# POWER_SUPPLY.net
KiCad netlist of a schematic drawn in Altium Designer
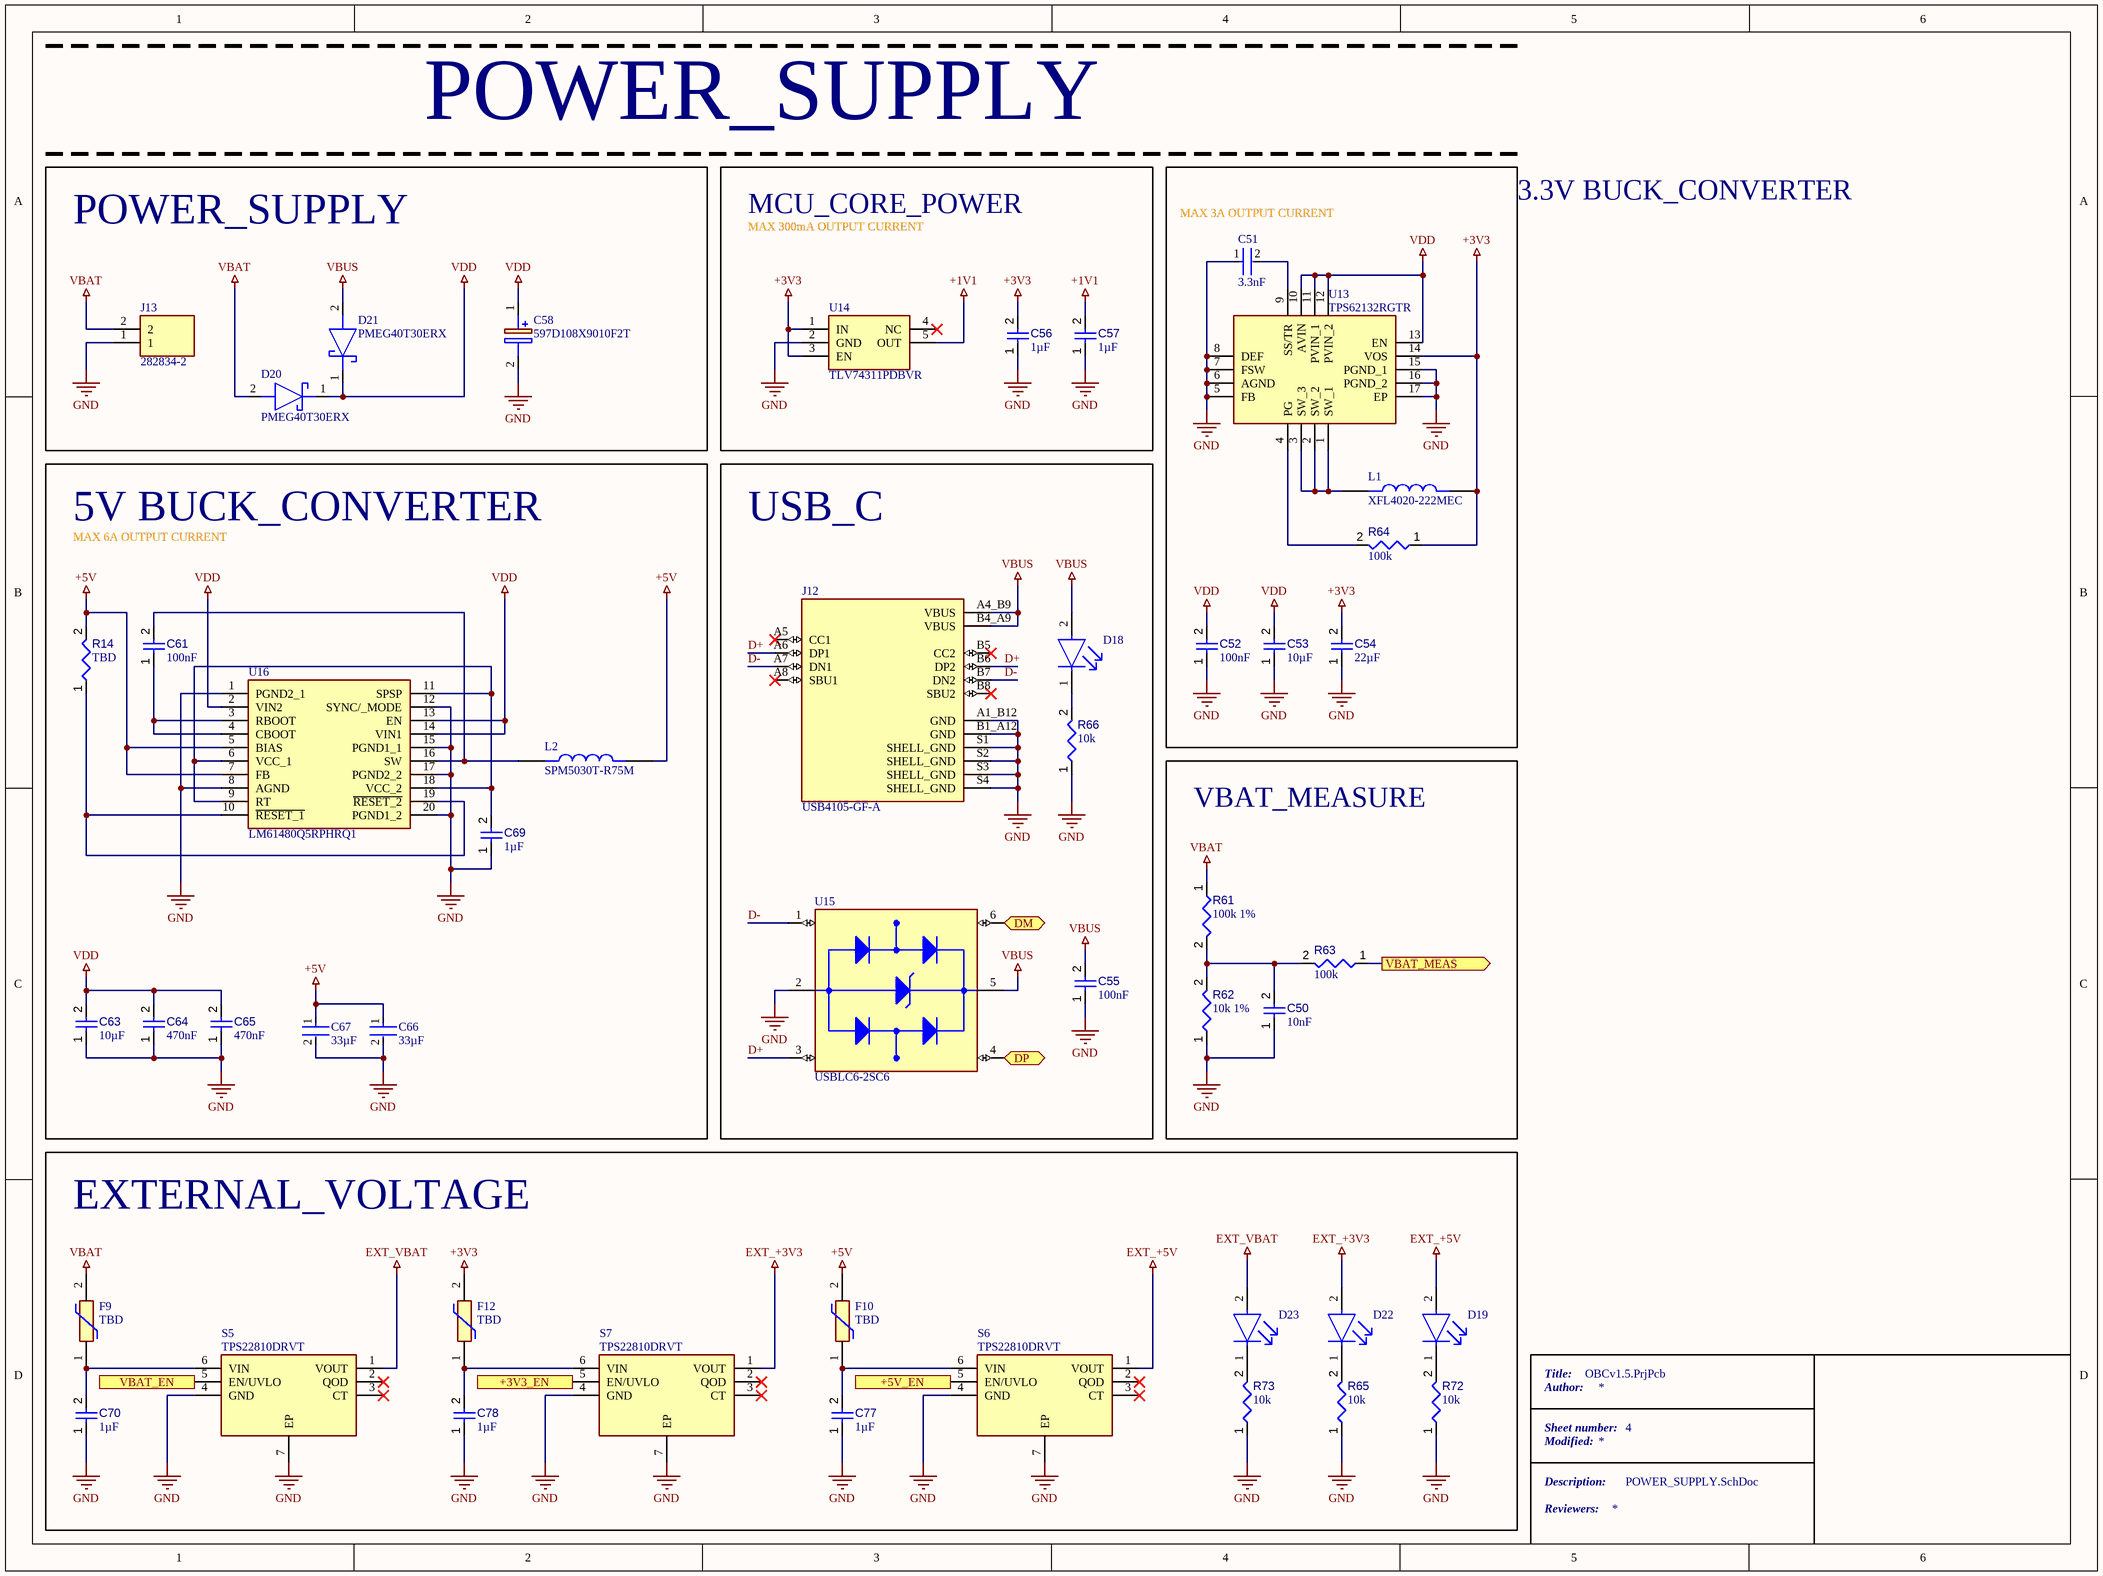
[diagram p0: POWER_SUPPLY.SchDoc]

(export (version "E")
  (design (tool "Eeschema 10.0.6"))
  (components
    (comp (ref "C50")
      (value "10nF")
      (footprint "CAPC0402(1005)60_L")
      (description "Chip Capacitor, 10nF +/-20%, 50V, 0402, Thickness 0.6 mm")
      (fields (field (name "TOLERANCE") "5%") (field (name "Comment") "Capacitor 10nF +/-20% 50V 0402"))
      (libsource (lib "PWr in Space team") (part "CAP-NP-2"))
    )
    (comp (ref "C51")
      (value "3.3nF")
      (footprint "FP-CL388-IPC_C")
      (description "Cap Ceramic 3.3nF 50V X7R ±10% SMD 0402 +125°C Paper T/R")
      (fields (field (name "TOLERANCE") "10%") (field (name "VOLTAGE") "50V"))
      (libsource (lib "Altium Content Vault") (part "b4654b650e69147ec39a6b967a45e02"))
    )
    (comp (ref "C52")
      (value "100nF")
      (footprint "CAPC0402(1005)60_L")
      (description "Chip Capacitor, 100nF +/-20%, 10V, 0402, Thickness 0.6 mm")
      (fields (field (name "TOLERANCE") "20%") (field (name "Comment") "Capacitor 100nF +/-20% 10V 0402"))
      (libsource (lib "PWr in Space team") (part "CAP-NP-2"))
    )
    (comp (ref "C53")
      (value "10µF")
      (footprint "CAPC0603(1608)100_L")
      (description "Chip Capacitor, 10µF +/-20%, 10V, 0603, Thickness 1 mm")
      (fields (field (name "TOLERANCE") "10%") (field (name "Comment") "Capacitor 10µF +/-20% 10V 0603"))
      (libsource (lib "PWr in Space team") (part "CAP-NP-2"))
    )
    (comp (ref "C54")
      (value "22µF")
      (footprint "CAPC0805(2012)145_L")
      (description "Chip Capacitor, 22µF +/-40%, 16V, 0805, Thickness 1.45 mm")
      (fields (field (name "TOLERANCE") "5%") (field (name "Comment") "Capacitor 22µF +/-40% 16V 0805"))
      (libsource (lib "PWr in Space team") (part "CAP-NP-2"))
    )
    (comp (ref "C55")
      (value "100nF")
      (footprint "CAPC0402(1005)60_L")
      (description "Chip Capacitor, 100nF +/-20%, 10V, 0402, Thickness 0.6 mm")
      (fields (field (name "TOLERANCE") "20%") (field (name "Comment") "Capacitor 100nF +/-20% 10V 0402"))
      (libsource (lib "PWr in Space team") (part "CAP-NP-2"))
    )
    (comp (ref "C56")
      (value "1µF")
      (footprint "CAPC0402(1005)60_L")
      (description "Chip Capacitor, 1µF +/-20%, 10V, 0402, Thickness 0.6 mm")
      (fields (field (name "TOLERANCE") "10%") (field (name "Comment") "Capacitor 1µF +/-20% 10V 0402"))
      (libsource (lib "PWr in Space team") (part "CAP-NP-2"))
    )
    (comp (ref "C57")
      (value "1µF")
      (footprint "CAPC0402(1005)60_L")
      (description "Chip Capacitor, 1µF +/-20%, 10V, 0402, Thickness 0.6 mm")
      (fields (field (name "TOLERANCE") "10%") (field (name "Comment") "Capacitor 1µF +/-20% 10V 0402"))
      (libsource (lib "PWr in Space team") (part "CAP-NP-2"))
    )
    (comp (ref "C58")
      (value "597D108X9010F2T")
      (footprint "SamacSys:CAPPC5760X510N")
      (description "Capacitor Polarised")
      (fields (field (name "MOUSER PART NUMBER") "71-597D108X9010F2T"))
      (libsource (lib "*") (part "597D108X9010F2T"))
    )
    (comp (ref "C61")
      (value "100nF")
      (footprint "CAPC0402(1005)60_L")
      (description "Chip Capacitor, 100nF +/-20%, 10V, 0402, Thickness 0.6 mm")
      (fields (field (name "TOLERANCE") "20%") (field (name "Comment") "Capacitor 100nF +/-20% 10V 0402"))
      (libsource (lib "PWr in Space team") (part "CAP-NP-2"))
    )
    (comp (ref "C63")
      (value "10µF")
      (footprint "CAPC0603(1608)100_L")
      (description "Chip Capacitor, 10µF +/-20%, 10V, 0603, Thickness 1 mm")
      (fields (field (name "TOLERANCE") "10%") (field (name "Comment") "Capacitor 10µF +/-20% 10V 0603"))
      (libsource (lib "PWr in Space team") (part "CAP-NP-2"))
    )
    (comp (ref "C64")
      (value "470nF")
      (footprint "CAPC0402(1005)60_L")
      (description "Chip Capacitor, 470nF +/-40%, 10V, 0402, Thickness 0.6 mm")
      (fields (field (name "TOLERANCE") "20%") (field (name "Comment") "Capacitor 470nF +/-40% 10V 0402"))
      (libsource (lib "PWr in Space team") (part "CAP-NP-2"))
    )
    (comp (ref "C65")
      (value "470nF")
      (footprint "CAPC0402(1005)60_L")
      (description "Chip Capacitor, 470nF +/-40%, 10V, 0402, Thickness 0.6 mm")
      (fields (field (name "TOLERANCE") "20%") (field (name "Comment") "Capacitor 470nF +/-40% 10V 0402"))
      (libsource (lib "PWr in Space team") (part "CAP-NP-2"))
    )
    (comp (ref "C66")
      (value "33µF")
      (footprint "FP-C2012-125-0_2-IPC_A")
      (description "Multilayer Ceramic Capacitors 33μF ±20% 6.3V X5R SMD 0805")
      (fields (field (name "TOLERANCE") "20%"))
      (libsource (lib "Altium Content Vault") (part "b4654b650e69147ec39a6b967a45e02"))
    )
    (comp (ref "C67")
      (value "33µF")
      (footprint "FP-C2012-125-0_2-IPC_A")
      (description "Multilayer Ceramic Capacitors 33μF ±20% 6.3V X5R SMD 0805")
      (fields (field (name "TOLERANCE") "20%"))
      (libsource (lib "Altium Content Vault") (part "b4654b650e69147ec39a6b967a45e02"))
    )
    (comp (ref "C69")
      (value "1µF")
      (footprint "CAPC0402(1005)60_L")
      (description "Chip Capacitor, 1µF +/-20%, 10V, 0402, Thickness 0.6 mm")
      (fields (field (name "TOLERANCE") "10%") (field (name "Comment") "Capacitor 1µF +/-20% 10V 0402"))
      (libsource (lib "PWr in Space team") (part "CAP-NP-2"))
    )
    (comp (ref "C70")
      (value "1µF")
      (footprint "CAPC0402(1005)60_L")
      (description "Chip Capacitor, 1µF +/-20%, 10V, 0402, Thickness 0.6 mm")
      (fields (field (name "TOLERANCE") "10%") (field (name "Comment") "Capacitor 1µF +/-20% 10V 0402"))
      (libsource (lib "PWr in Space team") (part "CAP-NP-2"))
    )
    (comp (ref "C77")
      (value "1µF")
      (footprint "CAPC0402(1005)60_L")
      (description "Chip Capacitor, 1µF +/-20%, 10V, 0402, Thickness 0.6 mm")
      (fields (field (name "TOLERANCE") "10%") (field (name "Comment") "Capacitor 1µF +/-20% 10V 0402"))
      (libsource (lib "PWr in Space team") (part "CAP-NP-2"))
    )
    (comp (ref "C78")
      (value "1µF")
      (footprint "CAPC0402(1005)60_L")
      (description "Chip Capacitor, 1µF +/-20%, 10V, 0402, Thickness 0.6 mm")
      (fields (field (name "TOLERANCE") "10%") (field (name "Comment") "Capacitor 1µF +/-20% 10V 0402"))
      (libsource (lib "PWr in Space team") (part "CAP-NP-2"))
    )
    (comp (ref "D18")
      (value "~")
      (footprint "FP-LTST-C191TBKT-MFG")
      (description "LED BLUE CLEAR CHIP SMD")
      (libsource (lib "Altium Content Vault") (part "8706943c75ba83719d021d2fdc84c58"))
    )
    (comp (ref "D19")
      (value "~")
      (footprint "FP-LTST-C191TBKT-MFG")
      (description "LED BLUE CLEAR CHIP SMD")
      (libsource (lib "Altium Content Vault") (part "8706943c75ba83719d021d2fdc84c58"))
    )
    (comp (ref "D20")
      (value "PMEG40T30ERX")
      (footprint "SamacSys:SODFL3517X110N")
      (description "Schottky Diode")
      (fields
        (field (name "MANUFACTURER_PART_NUMBER") "PMEG60T30ELRX")
        (field (name "MOUSER PART NUMBER") "771-PMEG60T30ELRX")
      )
      (libsource (lib "*") (part "PMEG60T30ELRX"))
    )
    (comp (ref "D21")
      (value "PMEG40T30ERX")
      (footprint "SamacSys:SODFL3517X110N")
      (description "Schottky Diode")
      (fields
        (field (name "MANUFACTURER_PART_NUMBER") "PMEG60T30ELRX")
        (field (name "MOUSER PART NUMBER") "771-PMEG60T30ELRX")
      )
      (libsource (lib "*") (part "PMEG60T30ELRX"))
    )
    (comp (ref "D22")
      (value "~")
      (footprint "FP-LTST-C191TBKT-MFG")
      (description "LED BLUE CLEAR CHIP SMD")
      (libsource (lib "Altium Content Vault") (part "8706943c75ba83719d021d2fdc84c58"))
    )
    (comp (ref "D23")
      (value "~")
      (footprint "FP-LTST-C191TBKT-MFG")
      (description "LED BLUE CLEAR CHIP SMD")
      (libsource (lib "Altium Content Vault") (part "8706943c75ba83719d021d2fdc84c58"))
    )
    (comp (ref "F9")
      (value "TBD")
      (footprint "SamacSys:0402L010SLKR")
      (description "Resettable Fuse")
      (fields
        (field (name "MANUFACTURER_PART_NUMBER") "0402L100SLKR")
        (field (name "MOUSER PART NUMBER") "576-0402L100SLKR")
      )
      (libsource (lib "*") (part "0402L100SLKR"))
    )
    (comp (ref "F10")
      (value "TBD")
      (footprint "SamacSys:0402L010SLKR")
      (description "Resettable Fuse")
      (fields
        (field (name "MANUFACTURER_PART_NUMBER") "0402L100SLKR")
        (field (name "MOUSER PART NUMBER") "576-0402L100SLKR")
      )
      (libsource (lib "*") (part "0402L100SLKR"))
    )
    (comp (ref "F12")
      (value "TBD")
      (footprint "SamacSys:0402L010SLKR")
      (description "Resettable Fuse")
      (fields
        (field (name "MANUFACTURER_PART_NUMBER") "0402L100SLKR")
        (field (name "MOUSER PART NUMBER") "576-0402L100SLKR")
      )
      (libsource (lib "*") (part "0402L100SLKR"))
    )
    (comp (ref "J12")
      (value "USB4105-GF-A")
      (footprint "GCT_USB4105-GF-A")
      (fields (field (name "MF") "{'manufacturer': u'GCT'}"))
      (libsource (lib "SnapEDA_Library") (part "USB4105-GF-A"))
    )
    (comp (ref "J13")
      (value "282834-2")
      (footprint "SamacSys:282834-2_1")
      (description "Connector")
      (fields (field (name "MOUSER PART NUMBER") "571-282834-2"))
      (libsource (lib "*") (part "282834-2"))
    )
    (comp (ref "L1")
      (value "XFL4020-222MEC")
      (footprint "IND_XFL4020-102MEC")
      (description "Power inductor, shielded, 20% tol, SMT, RoHS, halogen free")
      (fields (field (name "MF") "{'manufacturer': u'Coilcraft'}") (field (name "MP") "XFL4020-102MEC"))
      (libsource (lib "SnapEDA_Library") (part "XFL4020-102MEC"))
    )
    (comp (ref "L2")
      (value "SPM5030T-R75M")
      (footprint "IND_SPM5030T-R75M")
      (fields (field (name "MF") "{'manufacturer': u'TDK'}"))
      (libsource (lib "SnapEDA_Library") (part "SPM5030T-R75M"))
    )
    (comp (ref "R14")
      (value "TBD")
      (footprint "RESC0402(1005)_L")
      (fields (field (name "TOLERANCE") "1%") (field (name "POWER") "63mW"))
      (libsource (lib "PWr in Space team") (part "RES-2"))
    )
    (comp (ref "R61")
      (value "100k 1%")
      (footprint "RESC0402(1005)_L")
      (description "Chip Resistor, 100 kOhms, +/-1 %, 63 mW, -55 to 155 degC, 0402")
      (fields (field (name "TOLERANCE") "1%") (field (name "POWER") "63mW"))
      (libsource (lib "PWr in Space team") (part "RES-2"))
    )
    (comp (ref "R62")
      (value "10k 1%")
      (footprint "RESC0402(1005)_L")
      (description "Chip Resistor, 10 kOhms, +/-1 %, 63 mW, -55 to 125 degC, 0402")
      (fields (field (name "POWER") "63mW") (field (name "TOLERANCE") "1%"))
      (libsource (lib "PWr in Space team") (part "RES-2"))
    )
    (comp (ref "R63")
      (value "100k")
      (footprint "RESC0402(1005)_L")
      (description "Chip Resistor, 100 kOhms, +/-1 %, 63 mW, -55 to 155 degC, 0402")
      (fields (field (name "TOLERANCE") "1%") (field (name "POWER") "63mW"))
      (libsource (lib "PWr in Space team") (part "RES-2"))
    )
    (comp (ref "R64")
      (value "100k")
      (footprint "RESC0402(1005)_L")
      (description "Chip Resistor, 100 kOhms, +/-1 %, 63 mW, -55 to 155 degC, 0402")
      (fields (field (name "TOLERANCE") "1%") (field (name "POWER") "63mW"))
      (libsource (lib "PWr in Space team") (part "RES-2"))
    )
    (comp (ref "R65")
      (value "10k")
      (footprint "RESC0402(1005)_L")
      (description "Chip Resistor, 10 kOhms, +/-1 %, 63 mW, -55 to 125 degC, 0402")
      (fields (field (name "POWER") "63mW") (field (name "TOLERANCE") "1%"))
      (libsource (lib "PWr in Space team") (part "RES-2"))
    )
    (comp (ref "R66")
      (value "10k")
      (footprint "RESC0402(1005)_L")
      (description "Chip Resistor, 10 kOhms, +/-1 %, 63 mW, -55 to 125 degC, 0402")
      (fields (field (name "POWER") "63mW") (field (name "TOLERANCE") "1%"))
      (libsource (lib "PWr in Space team") (part "RES-2"))
    )
    (comp (ref "R72")
      (value "10k")
      (footprint "RESC0402(1005)_L")
      (description "Chip Resistor, 10 kOhms, +/-1 %, 63 mW, -55 to 125 degC, 0402")
      (fields (field (name "POWER") "63mW") (field (name "TOLERANCE") "1%"))
      (libsource (lib "PWr in Space team") (part "RES-2"))
    )
    (comp (ref "R73")
      (value "10k")
      (footprint "RESC0402(1005)_L")
      (description "Chip Resistor, 10 kOhms, +/-1 %, 63 mW, -55 to 125 degC, 0402")
      (fields (field (name "POWER") "63mW") (field (name "TOLERANCE") "1%"))
      (libsource (lib "PWr in Space team") (part "RES-2"))
    )
    (comp (ref "S5")
      (value "TPS22810DRVT")
      (footprint "SamacSys:SON65P200X200X80-7N")
      (description "Switch")
      (fields (field (name "MOUSER PART NUMBER") "595-TPS22810DRVT"))
      (libsource (lib "*") (part "TPS22810DRVT"))
    )
    (comp (ref "S6")
      (value "TPS22810DRVT")
      (footprint "SamacSys:SON65P200X200X80-7N")
      (description "Switch")
      (fields (field (name "MOUSER PART NUMBER") "595-TPS22810DRVT"))
      (libsource (lib "*") (part "TPS22810DRVT"))
    )
    (comp (ref "S7")
      (value "TPS22810DRVT")
      (footprint "SamacSys:SON65P200X200X80-7N")
      (description "Switch")
      (fields (field (name "MOUSER PART NUMBER") "595-TPS22810DRVT"))
      (libsource (lib "*") (part "TPS22810DRVT"))
    )
    (comp (ref "U13")
      (value "TPS62132RGTR")
      (footprint "SamacSys:QFN50P300X300X100-17N-D")
      (description "Integrated Circuit")
      (fields (field (name "MOUSER PART NUMBER") "595-TPS62132RGTR"))
      (libsource (lib "*") (part "TPS62132RGTR"))
    )
    (comp (ref "U14")
      (value "TLV74311PDBVR")
      (footprint "SamacSys:SOT95P280X145-5N")
      (description "Integrated Circuit")
      (fields
        (field (name "MANUFACTURER_PART_NUMBER") "TLV70311DBVR")
        (field (name "MOUSER PART NUMBER") "595-TLV70311DBVR")
      )
      (libsource (lib "*") (part "TLV70311DBVR"))
    )
    (comp (ref "U15")
      (value "USBLC6-2SC6")
      (footprint "SOT95P280X145-6N")
      (fields (field (name "MF") "{'manufacturer': u'STMicroelectronics'}"))
      (libsource (lib "SnapEDA_Library") (part "USBLC6-2SC6"))
    )
    (comp (ref "U16")
      (value "LM61480Q5RPHRQ1")
      (footprint "SamacSys:LM61480Q4RPHRQ1")
      (description "Integrated Circuit")
      (fields (field (name "MOUSER PART NUMBER") "595-LM61480Q5RPHRQ1"))
      (libsource (lib "*") (part "LM61480Q5RPHRQ1"))
    )
  )
  (nets
    (net (code "1") (name "+1V1") (class "Default")
      (node (ref "C57") (pin "2") (pinfunction "2_2") (pintype "passive"))
      (node (ref "U14") (pin "5") (pinfunction "OUT_5") (pintype "passive"))
    )
    (net (code "2") (name "+3V3") (class "Default")
      (node (ref "C54") (pin "2") (pinfunction "2_2") (pintype "passive"))
      (node (ref "C56") (pin "2") (pinfunction "2_2") (pintype "passive"))
      (node (ref "F12") (pin "2") (pinfunction "2_2") (pintype "passive"))
      (node (ref "L1") (pin "1") (pinfunction "1_1") (pintype "passive"))
      (node (ref "R64") (pin "1") (pinfunction "1_1") (pintype "passive"))
      (node (ref "U13") (pin "14") (pinfunction "VOS_14") (pintype "passive"))
      (node (ref "U14") (pin "1") (pinfunction "IN_1") (pintype "passive"))
      (node (ref "U14") (pin "3") (pinfunction "EN_3") (pintype "passive"))
    )
    (net (code "3") (name "+5V") (class "Default")
      (node (ref "C66") (pin "1") (pinfunction "1_1") (pintype "passive"))
      (node (ref "C67") (pin "1") (pinfunction "1_1") (pintype "passive"))
      (node (ref "F10") (pin "2") (pinfunction "2_2") (pintype "passive"))
      (node (ref "L2") (pin "2") (pinfunction "2_2") (pintype "passive"))
      (node (ref "R14") (pin "2") (pinfunction "2_2") (pintype "passive"))
      (node (ref "U16") (pin "5") (pinfunction "BIAS_5") (pintype "passive"))
      (node (ref "U16") (pin "7") (pinfunction "FB_7") (pintype "passive"))
    )
    (net (code "4") (name "/+3V3_EN") (class "Default")
      (node (ref "S7") (pin "5") (pinfunction "EN/UVLO_5") (pintype "passive"))
    )
    (net (code "5") (name "/+5V_EN") (class "Default")
      (node (ref "S6") (pin "5") (pinfunction "EN/UVLO_5") (pintype "passive"))
    )
    (net (code "6") (name "/D+") (class "Default")
      (node (ref "J12") (pin "A6") (pinfunction "DP1_A6") (pintype "bidirectional"))
      (node (ref "J12") (pin "B6") (pinfunction "DP2_B6") (pintype "bidirectional"))
      (node (ref "U15") (pin "3") (pinfunction "I/O2_IN_3") (pintype "bidirectional"))
    )
    (net (code "7") (name "/D-") (class "Default")
      (node (ref "J12") (pin "A7") (pinfunction "DN1_A7") (pintype "bidirectional"))
      (node (ref "J12") (pin "B7") (pinfunction "DN2_B7") (pintype "bidirectional"))
      (node (ref "U15") (pin "1") (pinfunction "I/O1_IN_1") (pintype "bidirectional"))
    )
    (net (code "8") (name "/DM") (class "Default")
      (node (ref "U15") (pin "6") (pinfunction "I/O1_OUT_6") (pintype "bidirectional"))
    )
    (net (code "9") (name "/DP") (class "Default")
      (node (ref "U15") (pin "4") (pinfunction "I/O2_OUT_4") (pintype "bidirectional"))
    )
    (net (code "10") (name "/VBAT_EN") (class "Default")
      (node (ref "S5") (pin "5") (pinfunction "EN/UVLO_5") (pintype "passive"))
    )
    (net (code "11") (name "/VBAT_MEAS") (class "Default")
      (node (ref "R63") (pin "1") (pinfunction "1_1") (pintype "passive"))
    )
    (net (code "12") (name "EXT_+3V3") (class "Default")
      (node (ref "D22") (pin "2") (pinfunction "A_2") (pintype "passive"))
      (node (ref "S7") (pin "1") (pinfunction "VOUT_1") (pintype "passive"))
    )
    (net (code "13") (name "EXT_+5V") (class "Default")
      (node (ref "D19") (pin "2") (pinfunction "A_2") (pintype "passive"))
      (node (ref "S6") (pin "1") (pinfunction "VOUT_1") (pintype "passive"))
    )
    (net (code "14") (name "EXT_VBAT") (class "Default")
      (node (ref "D23") (pin "2") (pinfunction "A_2") (pintype "passive"))
      (node (ref "S5") (pin "1") (pinfunction "VOUT_1") (pintype "passive"))
    )
    (net (code "15") (name "GND") (class "Default")
      (node (ref "C50") (pin "1") (pinfunction "1_1") (pintype "passive"))
      (node (ref "C51") (pin "1") (pinfunction "1_1") (pintype "passive"))
      (node (ref "C52") (pin "1") (pinfunction "1_1") (pintype "passive"))
      (node (ref "C53") (pin "1") (pinfunction "1_1") (pintype "passive"))
      (node (ref "C54") (pin "1") (pinfunction "1_1") (pintype "passive"))
      (node (ref "C55") (pin "1") (pinfunction "1_1") (pintype "passive"))
      (node (ref "C56") (pin "1") (pinfunction "1_1") (pintype "passive"))
      (node (ref "C57") (pin "1") (pinfunction "1_1") (pintype "passive"))
      (node (ref "C58") (pin "2") (pinfunction "-_2") (pintype "passive"))
      (node (ref "C63") (pin "1") (pinfunction "1_1") (pintype "passive"))
      (node (ref "C64") (pin "1") (pinfunction "1_1") (pintype "passive"))
      (node (ref "C65") (pin "1") (pinfunction "1_1") (pintype "passive"))
      (node (ref "C66") (pin "2") (pinfunction "2_2") (pintype "passive"))
      (node (ref "C67") (pin "2") (pinfunction "2_2") (pintype "passive"))
      (node (ref "C69") (pin "1") (pinfunction "1_1") (pintype "passive"))
      (node (ref "C70") (pin "1") (pinfunction "1_1") (pintype "passive"))
      (node (ref "C77") (pin "1") (pinfunction "1_1") (pintype "passive"))
      (node (ref "C78") (pin "1") (pinfunction "1_1") (pintype "passive"))
      (node (ref "J12") (pin "A1_B12") (pinfunction "GND_A1_B12") (pintype "power_in"))
      (node (ref "J12") (pin "B1_A12") (pinfunction "GND_B1_A12") (pintype "power_in"))
      (node (ref "J12") (pin "S1") (pinfunction "SHELL_GND_S1") (pintype "power_in"))
      (node (ref "J12") (pin "S2") (pinfunction "SHELL_GND_S2") (pintype "power_in"))
      (node (ref "J12") (pin "S3") (pinfunction "SHELL_GND_S3") (pintype "power_in"))
      (node (ref "J12") (pin "S4") (pinfunction "SHELL_GND_S4") (pintype "power_in"))
      (node (ref "J13") (pin "1") (pinfunction "1_1") (pintype "passive"))
      (node (ref "R62") (pin "1") (pinfunction "1_1") (pintype "passive"))
      (node (ref "R65") (pin "1") (pinfunction "1_1") (pintype "passive"))
      (node (ref "R66") (pin "1") (pinfunction "1_1") (pintype "passive"))
      (node (ref "R72") (pin "1") (pinfunction "1_1") (pintype "passive"))
      (node (ref "R73") (pin "1") (pinfunction "1_1") (pintype "passive"))
      (node (ref "S5") (pin "4") (pinfunction "GND_4") (pintype "passive"))
      (node (ref "S5") (pin "7") (pinfunction "EP_7") (pintype "passive"))
      (node (ref "S6") (pin "4") (pinfunction "GND_4") (pintype "passive"))
      (node (ref "S6") (pin "7") (pinfunction "EP_7") (pintype "passive"))
      (node (ref "S7") (pin "4") (pinfunction "GND_4") (pintype "passive"))
      (node (ref "S7") (pin "7") (pinfunction "EP_7") (pintype "passive"))
      (node (ref "U13") (pin "15") (pinfunction "PGND_1_15") (pintype "passive"))
      (node (ref "U13") (pin "16") (pinfunction "PGND_2_16") (pintype "passive"))
      (node (ref "U13") (pin "17") (pinfunction "EP_17") (pintype "passive"))
      (node (ref "U13") (pin "5") (pinfunction "FB_5") (pintype "passive"))
      (node (ref "U13") (pin "6") (pinfunction "AGND_6") (pintype "passive"))
      (node (ref "U13") (pin "7") (pinfunction "FSW_7") (pintype "passive"))
      (node (ref "U13") (pin "8") (pinfunction "DEF_8") (pintype "passive"))
      (node (ref "U14") (pin "2") (pinfunction "GND_2") (pintype "passive"))
      (node (ref "U15") (pin "2") (pinfunction "GND_2") (pintype "power_in"))
      (node (ref "U16") (pin "1") (pinfunction "PGND2_1_1") (pintype "passive"))
      (node (ref "U16") (pin "12") (pinfunction "SYNC/_MODE_12") (pintype "passive"))
      (node (ref "U16") (pin "15") (pinfunction "PGND1_1_15") (pintype "passive"))
      (node (ref "U16") (pin "17") (pinfunction "PGND2_2_17") (pintype "passive"))
      (node (ref "U16") (pin "20") (pinfunction "PGND1_2_20") (pintype "passive"))
      (node (ref "U16") (pin "8") (pinfunction "AGND_8") (pintype "passive"))
    )
    (net (code "16") (name "Net-(C50-Pad2)") (class "Default")
      (node (ref "C50") (pin "2") (pinfunction "2_2") (pintype "passive"))
      (node (ref "R61") (pin "2") (pinfunction "2_2") (pintype "passive"))
      (node (ref "R62") (pin "2") (pinfunction "2_2") (pintype "passive"))
      (node (ref "R63") (pin "2") (pinfunction "2_2") (pintype "passive"))
    )
    (net (code "17") (name "Net-(D18-C)") (class "Default")
      (node (ref "D18") (pin "1") (pinfunction "C_1") (pintype "passive"))
      (node (ref "R66") (pin "2") (pinfunction "2_2") (pintype "passive"))
    )
    (net (code "18") (name "Net-(D19-C)") (class "Default")
      (node (ref "D19") (pin "1") (pinfunction "C_1") (pintype "passive"))
      (node (ref "R72") (pin "2") (pinfunction "2_2") (pintype "passive"))
    )
    (net (code "19") (name "Net-(D22-C)") (class "Default")
      (node (ref "D22") (pin "1") (pinfunction "C_1") (pintype "passive"))
      (node (ref "R65") (pin "2") (pinfunction "2_2") (pintype "passive"))
    )
    (net (code "20") (name "Net-(D23-C)") (class "Default")
      (node (ref "D23") (pin "1") (pinfunction "C_1") (pintype "passive"))
      (node (ref "R73") (pin "2") (pinfunction "2_2") (pintype "passive"))
    )
    (net (code "21") (name "Net-(S5-VIN)") (class "Default")
      (node (ref "C70") (pin "2") (pinfunction "2_2") (pintype "passive"))
      (node (ref "F9") (pin "1") (pinfunction "1_1") (pintype "passive"))
      (node (ref "S5") (pin "6") (pinfunction "VIN_6") (pintype "passive"))
    )
    (net (code "22") (name "Net-(S6-VIN)") (class "Default")
      (node (ref "C77") (pin "2") (pinfunction "2_2") (pintype "passive"))
      (node (ref "F10") (pin "1") (pinfunction "1_1") (pintype "passive"))
      (node (ref "S6") (pin "6") (pinfunction "VIN_6") (pintype "passive"))
    )
    (net (code "23") (name "Net-(S7-VIN)") (class "Default")
      (node (ref "C78") (pin "2") (pinfunction "2_2") (pintype "passive"))
      (node (ref "F12") (pin "1") (pinfunction "1_1") (pintype "passive"))
      (node (ref "S7") (pin "6") (pinfunction "VIN_6") (pintype "passive"))
    )
    (net (code "24") (name "Net-(U13-PG)") (class "Default")
      (node (ref "R64") (pin "2") (pinfunction "2_2") (pintype "passive"))
      (node (ref "U13") (pin "4") (pinfunction "PG_4") (pintype "passive"))
    )
    (net (code "25") (name "Net-(U13-SS{slash}TR)") (class "Default")
      (node (ref "C51") (pin "2") (pinfunction "2_2") (pintype "passive"))
      (node (ref "U13") (pin "9") (pinfunction "SS/TR_9") (pintype "passive"))
    )
    (net (code "26") (name "Net-(U13-SW_1)") (class "Default")
      (node (ref "L1") (pin "2") (pinfunction "2_2") (pintype "passive"))
      (node (ref "U13") (pin "1") (pinfunction "SW_1_1") (pintype "passive"))
      (node (ref "U13") (pin "2") (pinfunction "SW_2_2") (pintype "passive"))
      (node (ref "U13") (pin "3") (pinfunction "SW_3_3") (pintype "passive"))
    )
    (net (code "27") (name "Net-(U16-CBOOT)") (class "Default")
      (node (ref "C61") (pin "1") (pinfunction "1_1") (pintype "passive"))
      (node (ref "U16") (pin "3") (pinfunction "RBOOT_3") (pintype "passive"))
      (node (ref "U16") (pin "4") (pinfunction "CBOOT_4") (pintype "passive"))
    )
    (net (code "28") (name "Net-(U16-RT)") (class "Default")
      (node (ref "C69") (pin "2") (pinfunction "2_2") (pintype "passive"))
      (node (ref "U16") (pin "11") (pinfunction "SPSP_11") (pintype "passive"))
      (node (ref "U16") (pin "18") (pinfunction "VCC_2_18") (pintype "passive"))
      (node (ref "U16") (pin "6") (pinfunction "VCC_1_6") (pintype "passive"))
      (node (ref "U16") (pin "9") (pinfunction "RT_9") (pintype "passive"))
    )
    (net (code "29") (name "Net-(U16-SW)") (class "Default")
      (node (ref "C61") (pin "2") (pinfunction "2_2") (pintype "passive"))
      (node (ref "L2") (pin "1") (pinfunction "1_1") (pintype "passive"))
      (node (ref "U16") (pin "16") (pinfunction "SW_16") (pintype "passive"))
    )
    (net (code "30") (name "Net-(U16-~{RESET_1})") (class "Default")
      (node (ref "R14") (pin "1") (pinfunction "1_1") (pintype "passive"))
      (node (ref "U16") (pin "10") (pinfunction "~{RESET_1}_10") (pintype "passive"))
      (node (ref "U16") (pin "19") (pinfunction "~{RESET_2}_19") (pintype "passive"))
    )
    (net (code "31") (name "VBAT") (class "Default")
      (node (ref "D20") (pin "2") (pinfunction "A_2") (pintype "passive"))
      (node (ref "F9") (pin "2") (pinfunction "2_2") (pintype "passive"))
      (node (ref "J13") (pin "2") (pinfunction "2_2") (pintype "passive"))
      (node (ref "R61") (pin "1") (pinfunction "1_1") (pintype "passive"))
    )
    (net (code "32") (name "VBUS") (class "Default")
      (node (ref "C55") (pin "2") (pinfunction "2_2") (pintype "passive"))
      (node (ref "D18") (pin "2") (pinfunction "A_2") (pintype "passive"))
      (node (ref "D21") (pin "2") (pinfunction "A_2") (pintype "passive"))
      (node (ref "J12") (pin "A4_B9") (pinfunction "VBUS_A4_B9") (pintype "power_in"))
      (node (ref "J12") (pin "B4_A9") (pinfunction "VBUS_B4_A9") (pintype "power_in"))
      (node (ref "U15") (pin "5") (pinfunction "VBUS_5") (pintype "power_in"))
    )
    (net (code "33") (name "VDD") (class "Default")
      (node (ref "C52") (pin "2") (pinfunction "2_2") (pintype "passive"))
      (node (ref "C53") (pin "2") (pinfunction "2_2") (pintype "passive"))
      (node (ref "C58") (pin "1") (pinfunction "+_1") (pintype "passive"))
      (node (ref "C63") (pin "2") (pinfunction "2_2") (pintype "passive"))
      (node (ref "C64") (pin "2") (pinfunction "2_2") (pintype "passive"))
      (node (ref "C65") (pin "2") (pinfunction "2_2") (pintype "passive"))
      (node (ref "D20") (pin "1") (pinfunction "K_1") (pintype "passive"))
      (node (ref "D21") (pin "1") (pinfunction "K_1") (pintype "passive"))
      (node (ref "U13") (pin "10") (pinfunction "AVIN_10") (pintype "passive"))
      (node (ref "U13") (pin "11") (pinfunction "PVIN_1_11") (pintype "passive"))
      (node (ref "U13") (pin "12") (pinfunction "PVIN_2_12") (pintype "passive"))
      (node (ref "U13") (pin "13") (pinfunction "EN_13") (pintype "passive"))
      (node (ref "U16") (pin "13") (pinfunction "EN_13") (pintype "passive"))
      (node (ref "U16") (pin "14") (pinfunction "VIN1_14") (pintype "passive"))
      (node (ref "U16") (pin "2") (pinfunction "VIN2_2") (pintype "passive"))
    )
    (net (code "34") (name "unconnected-(J12-CC1-PadA5)") (class "Default")
      (node (ref "J12") (pin "A5") (pinfunction "CC1_A5") (pintype "bidirectional+no_connect"))
    )
    (net (code "35") (name "unconnected-(J12-CC2-PadB5)") (class "Default")
      (node (ref "J12") (pin "B5") (pinfunction "CC2_B5") (pintype "bidirectional+no_connect"))
    )
    (net (code "36") (name "unconnected-(J12-SBU1-PadA8)") (class "Default")
      (node (ref "J12") (pin "A8") (pinfunction "SBU1_A8") (pintype "bidirectional+no_connect"))
    )
    (net (code "37") (name "unconnected-(J12-SBU2-PadB8)") (class "Default")
      (node (ref "J12") (pin "B8") (pinfunction "SBU2_B8") (pintype "bidirectional+no_connect"))
    )
    (net (code "38") (name "unconnected-(S5-CT-Pad3)") (class "Default")
      (node (ref "S5") (pin "3") (pinfunction "CT_3") (pintype "passive+no_connect"))
    )
    (net (code "39") (name "unconnected-(S5-QOD-Pad2)") (class "Default")
      (node (ref "S5") (pin "2") (pinfunction "QOD_2") (pintype "passive+no_connect"))
    )
    (net (code "40") (name "unconnected-(S6-CT-Pad3)") (class "Default")
      (node (ref "S6") (pin "3") (pinfunction "CT_3") (pintype "passive+no_connect"))
    )
    (net (code "41") (name "unconnected-(S6-QOD-Pad2)") (class "Default")
      (node (ref "S6") (pin "2") (pinfunction "QOD_2") (pintype "passive+no_connect"))
    )
    (net (code "42") (name "unconnected-(S7-CT-Pad3)") (class "Default")
      (node (ref "S7") (pin "3") (pinfunction "CT_3") (pintype "passive+no_connect"))
    )
    (net (code "43") (name "unconnected-(S7-QOD-Pad2)") (class "Default")
      (node (ref "S7") (pin "2") (pinfunction "QOD_2") (pintype "passive+no_connect"))
    )
    (net (code "44") (name "unconnected-(U14-NC-Pad4)") (class "Default")
      (node (ref "U14") (pin "4") (pinfunction "NC_4") (pintype "passive+no_connect"))
    )
  )
)
